# WeatherStation.net
KiCad netlist of a schematic drawn in EAGLE
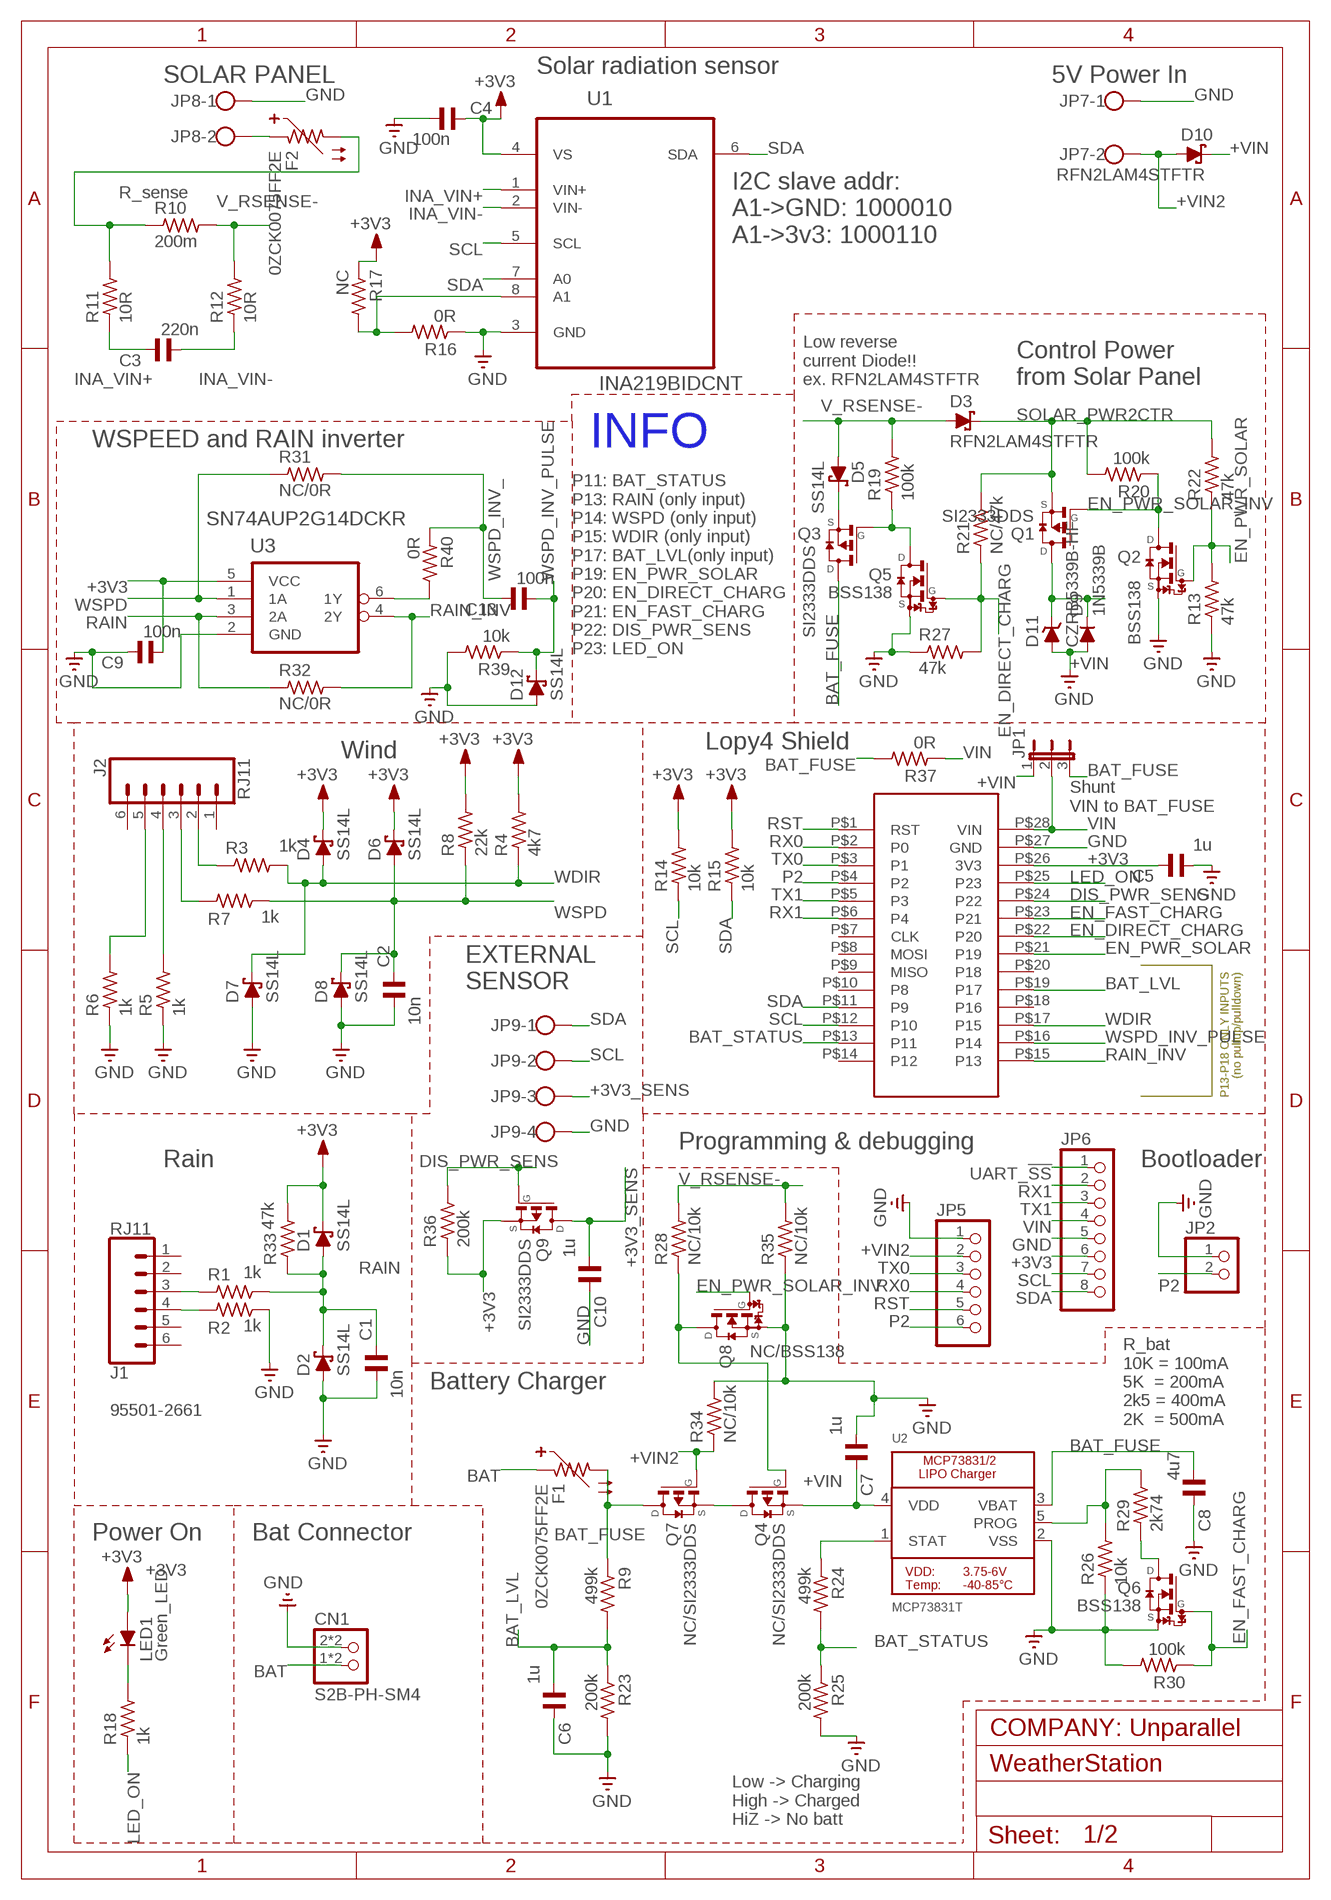
[diagram p0: schematic, sheet 1]
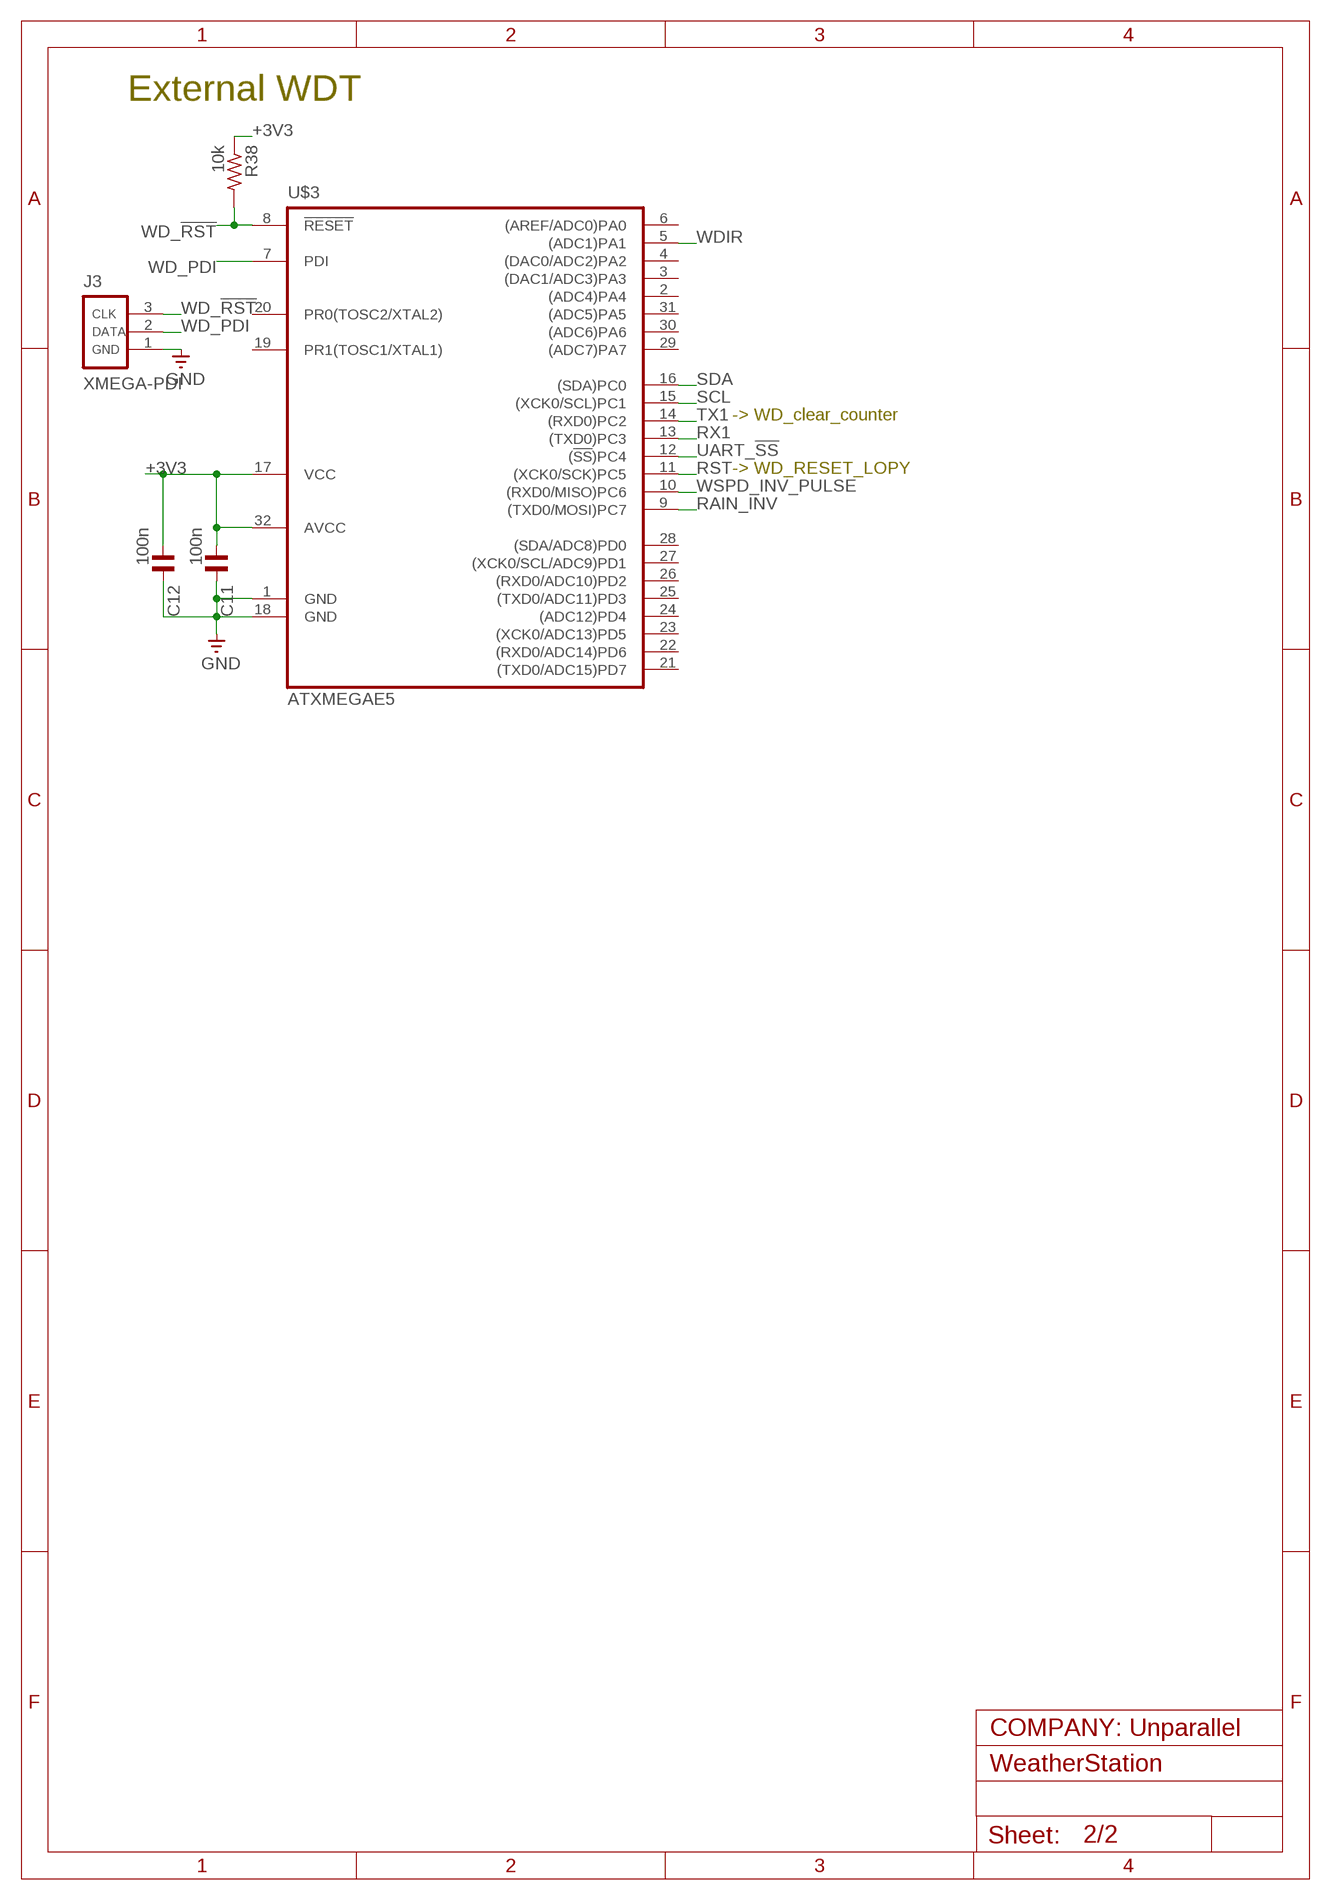
[diagram p1: schematic, sheet 2]

(export (version "E")
  (design (tool "Eeschema 10.0.6"))
  (components
    (comp (ref "C11")
      (value "100n")
      (footprint "eagle-import:C0603")
      (libsource (lib "eagle-import") (part "C-EUC0603"))
    )
    (comp (ref "C12")
      (value "100n")
      (footprint "eagle-import:C0603")
      (libsource (lib "eagle-import") (part "C-EUC0603"))
    )
    (comp (ref "J3")
      (value "XMEGA-PDI")
      (footprint "eagle-import:HDR-MA02-3P_P0.05_FABIO")
      (libsource (lib "eagle-import") (part "XMEGA-PDI-3_FABIO"))
    )
    (comp (ref "R38")
      (value "10k")
      (footprint "eagle-import:R0603")
      (libsource (lib "eagle-import") (part "R-EU_R0603"))
    )
    (comp (ref "U$3")
      (value "ATXMEGAE5")
      (footprint "eagle-import:TQFP32_PROTO_SLIM")
      (libsource (lib "eagle-import") (part "ATXMEGAE5-AU_SLIM_AU"))
    )
    (comp (ref "C1")
      (value "10n")
      (footprint "eagle-import:C0603_C0805_PROTO_SLIM")
      (libsource (lib "eagle-import") (part "C-EUC0603/C0805_PROTO_SLIM"))
    )
    (comp (ref "C2")
      (value "10n")
      (footprint "eagle-import:C0603_C0805_PROTO_SLIM")
      (libsource (lib "eagle-import") (part "C-EUC0603/C0805_PROTO_SLIM"))
    )
    (comp (ref "C3")
      (value "220n")
      (footprint "eagle-import:C0603")
      (libsource (lib "eagle-import") (part "C-EUC0603"))
    )
    (comp (ref "C4")
      (value "100n")
      (footprint "eagle-import:C0603")
      (libsource (lib "eagle-import") (part "C-EUC0603"))
    )
    (comp (ref "C5")
      (value "1u")
      (footprint "eagle-import:C0603_C0805_PROTO_SLIM")
      (libsource (lib "eagle-import") (part "C-EUC0603/C0805_PROTO_SLIM"))
    )
    (comp (ref "C6")
      (value "1u")
      (footprint "eagle-import:C0603_C0805_PROTO_SLIM")
      (libsource (lib "eagle-import") (part "C-EUC0603/C0805_PROTO_SLIM"))
    )
    (comp (ref "C7")
      (value "1u")
      (footprint "eagle-import:C0603_C0805_PROTO_SLIM")
      (libsource (lib "eagle-import") (part "C-EUC0603/C0805_PROTO_SLIM"))
    )
    (comp (ref "C8")
      (value "4u7")
      (footprint "eagle-import:C0603_C0805_PROTO_SLIM")
      (libsource (lib "eagle-import") (part "C-EUC0603/C0805_PROTO_SLIM"))
    )
    (comp (ref "C9")
      (value "100n")
      (footprint "eagle-import:C0603")
      (libsource (lib "eagle-import") (part "C-EUC0603"))
    )
    (comp (ref "C10")
      (value "1u")
      (footprint "eagle-import:C0603_C0805_PROTO_SLIM")
      (libsource (lib "eagle-import") (part "C-EUC0603/C0805_PROTO_SLIM"))
    )
    (comp (ref "C13")
      (value "100n")
      (footprint "eagle-import:C0603")
      (libsource (lib "eagle-import") (part "C-EUC0603"))
    )
    (comp (ref "CN1")
      (value "S2B-PH-SM4")
      (footprint "eagle-import:JST-PH-2-SMT-RA_OK")
      (libsource (lib "eagle-import") (part "JST_2PINHOR_VER"))
    )
    (comp (ref "D1")
      (value "SS14L")
      (footprint "eagle-import:SUB_SMA_PROTO")
      (libsource (lib "eagle-import") (part "SCHOTTKY-DIODESUB_SMA_PROTO"))
    )
    (comp (ref "D2")
      (value "SS14L")
      (footprint "eagle-import:SUB_SMA_PROTO")
      (libsource (lib "eagle-import") (part "SCHOTTKY-DIODESUB_SMA_PROTO"))
    )
    (comp (ref "D3")
      (value "RFN2LAM4STFTR")
      (footprint "eagle-import:SMA_SOD-128_PROTO")
      (libsource (lib "eagle-import") (part "SCHOTTKY-DIODESMA_SOD-128_PROTO"))
    )
    (comp (ref "D4")
      (value "SS14L")
      (footprint "eagle-import:SUB_SMA_PROTO")
      (libsource (lib "eagle-import") (part "SCHOTTKY-DIODESUB_SMA_PROTO"))
    )
    (comp (ref "D5")
      (value "SS14L")
      (footprint "eagle-import:SUB_SMA_PROTO")
      (libsource (lib "eagle-import") (part "SCHOTTKY-DIODESUB_SMA_PROTO"))
    )
    (comp (ref "D6")
      (value "SS14L")
      (footprint "eagle-import:SUB_SMA_PROTO")
      (libsource (lib "eagle-import") (part "SCHOTTKY-DIODESUB_SMA_PROTO"))
    )
    (comp (ref "D7")
      (value "SS14L")
      (footprint "eagle-import:SUB_SMA_PROTO")
      (libsource (lib "eagle-import") (part "SCHOTTKY-DIODESUB_SMA_PROTO"))
    )
    (comp (ref "D8")
      (value "SS14L")
      (footprint "eagle-import:SUB_SMA_PROTO")
      (libsource (lib "eagle-import") (part "SCHOTTKY-DIODESUB_SMA_PROTO"))
    )
    (comp (ref "D9")
      (value "1N5339B")
      (footprint "eagle-import:DO15-12")
      (libsource (lib "eagle-import") (part "DIODE-DO15-12"))
    )
    (comp (ref "D10")
      (value "RFN2LAM4STFTR")
      (footprint "eagle-import:SMA_SOD-128_PROTO")
      (libsource (lib "eagle-import") (part "SCHOTTKY-DIODESMA_SOD-128_PROTO"))
    )
    (comp (ref "D11")
      (value "CZRB5339B-HF")
      (footprint "eagle-import:SMB_PROTO")
      (libsource (lib "eagle-import") (part "ZENER-DIODE-PROTO"))
    )
    (comp (ref "D12")
      (value "SS14L")
      (footprint "eagle-import:SUB_SMA_PROTO")
      (libsource (lib "eagle-import") (part "SCHOTTKY-DIODESUB_SMA_PROTO"))
    )
    (comp (ref "F1")
      (value "0ZCK0075FF2E")
      (footprint "eagle-import:R0603_R0805_PROTO_SLIM")
      (libsource (lib "eagle-import") (part "PTC-0603_0805_PROTO_SLIM"))
    )
    (comp (ref "F2")
      (value "0ZCK0075FF2E")
      (footprint "eagle-import:R0603_R0805_PROTO_SLIM")
      (libsource (lib "eagle-import") (part "PTC-0603_0805_PROTO_SLIM"))
    )
    (comp (ref "J1")
      (value "RJ11")
      (footprint "eagle-import:RJ11-6")
      (libsource (lib "eagle-import") (part "RJ11-6"))
    )
    (comp (ref "J2")
      (value "RJ11")
      (footprint "eagle-import:RJ11-6")
      (libsource (lib "eagle-import") (part "RJ11-6"))
    )
    (comp (ref "JP1")
      (value "JP2E-0805")
      (footprint "eagle-import:R0805_2")
      (libsource (lib "eagle-import") (part "JP2E-0805"))
    )
    (comp (ref "JP2")
      (value "PINHD-1X2")
      (footprint "eagle-import:1X02")
      (libsource (lib "eagle-import") (part "PINHD-1X2"))
    )
    (comp (ref "JP5")
      (value "PINHD-1X6")
      (footprint "eagle-import:1X06")
      (libsource (lib "eagle-import") (part "PINHD-1X6"))
    )
    (comp (ref "JP6")
      (value "PINHD-1X8")
      (footprint "eagle-import:1X08")
      (libsource (lib "eagle-import") (part "PINHD-1X8"))
    )
    (comp (ref "JP7")
      (value "W237-102")
      (footprint "eagle-import:W237-102")
      (libsource (lib "eagle-import") (part "W237-102"))
    )
    (comp (ref "JP8")
      (value "W237-102")
      (footprint "eagle-import:W237-102")
      (libsource (lib "eagle-import") (part "W237-102"))
    )
    (comp (ref "JP9")
      (value "W237-4")
      (footprint "eagle-import:W237-4")
      (libsource (lib "eagle-import") (part "W237-4"))
    )
    (comp (ref "LED1")
      (value "Green_LED")
      (footprint "eagle-import:CHIP-LED0805")
      (libsource (lib "eagle-import") (part "LEDCHIP-LED0805"))
    )
    (comp (ref "Q1")
      (value "SI2333DDS")
      (footprint "eagle-import:SOT23_PROTO_SLIM")
      (libsource (lib "eagle-import") (part "SI2333DDSPROTO_SLIM"))
    )
    (comp (ref "Q2")
      (value "BSS138")
      (footprint "eagle-import:SOT23_PROTO_SLIM")
      (libsource (lib "eagle-import") (part "NX7002AKPROTO_SLIM"))
    )
    (comp (ref "Q3")
      (value "SI2333DDS")
      (footprint "eagle-import:SOT23_PROTO_SLIM")
      (libsource (lib "eagle-import") (part "SI2333DDSPROTO_SLIM"))
    )
    (comp (ref "Q4")
      (value "NC/SI2333DDS")
      (footprint "eagle-import:SOT23_PROTO_SLIM")
      (libsource (lib "eagle-import") (part "SI2333DDSPROTO_SLIM"))
    )
    (comp (ref "Q5")
      (value "BSS138")
      (footprint "eagle-import:SOT23_PROTO_SLIM")
      (libsource (lib "eagle-import") (part "NX7002AKPROTO_SLIM"))
    )
    (comp (ref "Q6")
      (value "BSS138")
      (footprint "eagle-import:SOT23_PROTO_SLIM")
      (libsource (lib "eagle-import") (part "NX7002AKPROTO_SLIM"))
    )
    (comp (ref "Q7")
      (value "NC/SI2333DDS")
      (footprint "eagle-import:SOT23_PROTO_SLIM")
      (libsource (lib "eagle-import") (part "SI2333DDSPROTO_SLIM"))
    )
    (comp (ref "Q8")
      (value "NC/BSS138")
      (footprint "eagle-import:SOT23_PROTO_SLIM")
      (libsource (lib "eagle-import") (part "NX7002AKPROTO_SLIM"))
    )
    (comp (ref "Q9")
      (value "SI2333DDS")
      (footprint "eagle-import:SOT23_PROTO_SLIM")
      (libsource (lib "eagle-import") (part "SI2333DDSPROTO_SLIM"))
    )
    (comp (ref "R1")
      (value "1k")
      (footprint "eagle-import:R0603")
      (libsource (lib "eagle-import") (part "R-EU_R0603"))
    )
    (comp (ref "R2")
      (value "1k")
      (footprint "eagle-import:R0603")
      (libsource (lib "eagle-import") (part "R-EU_R0603"))
    )
    (comp (ref "R3")
      (value "1k")
      (footprint "eagle-import:R0603")
      (libsource (lib "eagle-import") (part "R-EU_R0603"))
    )
    (comp (ref "R4")
      (value "4k7")
      (footprint "eagle-import:R0603")
      (libsource (lib "eagle-import") (part "R-EU_R0603"))
    )
    (comp (ref "R5")
      (value "1k")
      (footprint "eagle-import:R0603")
      (libsource (lib "eagle-import") (part "R-EU_R0603"))
    )
    (comp (ref "R6")
      (value "1k")
      (footprint "eagle-import:R0603")
      (libsource (lib "eagle-import") (part "R-EU_R0603"))
    )
    (comp (ref "R7")
      (value "1k")
      (footprint "eagle-import:R0603")
      (libsource (lib "eagle-import") (part "R-EU_R0603"))
    )
    (comp (ref "R8")
      (value "22k")
      (footprint "eagle-import:R0603")
      (libsource (lib "eagle-import") (part "R-EU_R0603"))
    )
    (comp (ref "R9")
      (value "499k")
      (footprint "eagle-import:R0603_R0805_PROTO_SLIM")
      (libsource (lib "eagle-import") (part "R-EU_R0603/R0805_PROTO_SLIM"))
    )
    (comp (ref "R10")
      (value "200m")
      (footprint "eagle-import:R0603_R0805_PROTO_SLIM")
      (libsource (lib "eagle-import") (part "R-EU_R0603/R0805_PROTO_SLIM"))
    )
    (comp (ref "R11")
      (value "10R")
      (footprint "eagle-import:R0603")
      (libsource (lib "eagle-import") (part "R-EU_R0603"))
    )
    (comp (ref "R12")
      (value "10R")
      (footprint "eagle-import:R0603")
      (libsource (lib "eagle-import") (part "R-EU_R0603"))
    )
    (comp (ref "R13")
      (value "47k")
      (footprint "eagle-import:R0603")
      (libsource (lib "eagle-import") (part "R-EU_R0603"))
    )
    (comp (ref "R14")
      (value "10k")
      (footprint "eagle-import:R0603")
      (libsource (lib "eagle-import") (part "R-EU_R0603"))
    )
    (comp (ref "R15")
      (value "10k")
      (footprint "eagle-import:R0603")
      (libsource (lib "eagle-import") (part "R-EU_R0603"))
    )
    (comp (ref "R16")
      (value "0R")
      (footprint "eagle-import:R0603")
      (libsource (lib "eagle-import") (part "R-EU_R0603"))
    )
    (comp (ref "R17")
      (value "NC")
      (footprint "eagle-import:R0603")
      (libsource (lib "eagle-import") (part "R-EU_R0603"))
    )
    (comp (ref "R18")
      (value "1k")
      (footprint "eagle-import:R0603")
      (libsource (lib "eagle-import") (part "R-EU_R0603"))
    )
    (comp (ref "R19")
      (value "100k")
      (footprint "eagle-import:R0603")
      (libsource (lib "eagle-import") (part "R-EU_R0603"))
    )
    (comp (ref "R20")
      (value "100k")
      (footprint "eagle-import:R0603")
      (libsource (lib "eagle-import") (part "R-EU_R0603"))
    )
    (comp (ref "R21")
      (value "NC/47k")
      (footprint "eagle-import:R0603")
      (libsource (lib "eagle-import") (part "R-EU_R0603"))
    )
    (comp (ref "R22")
      (value "47k")
      (footprint "eagle-import:R0603")
      (libsource (lib "eagle-import") (part "R-EU_R0603"))
    )
    (comp (ref "R23")
      (value "200k")
      (footprint "eagle-import:R0603_R0805_PROTO_SLIM")
      (libsource (lib "eagle-import") (part "R-EU_R0603/R0805_PROTO_SLIM"))
    )
    (comp (ref "R24")
      (value "499k")
      (footprint "eagle-import:R0603_R0805_PROTO_SLIM")
      (libsource (lib "eagle-import") (part "R-EU_R0603/R0805_PROTO_SLIM"))
    )
    (comp (ref "R25")
      (value "200k")
      (footprint "eagle-import:R0603_R0805_PROTO_SLIM")
      (libsource (lib "eagle-import") (part "R-EU_R0603/R0805_PROTO_SLIM"))
    )
    (comp (ref "R26")
      (value "10k")
      (footprint "eagle-import:R0603")
      (libsource (lib "eagle-import") (part "R-EU_R0603"))
    )
    (comp (ref "R27")
      (value "47k")
      (footprint "eagle-import:R0603")
      (libsource (lib "eagle-import") (part "R-EU_R0603"))
    )
    (comp (ref "R28")
      (value "NC/10k")
      (footprint "eagle-import:R0603")
      (libsource (lib "eagle-import") (part "R-EU_R0603"))
    )
    (comp (ref "R29")
      (value "2k74")
      (footprint "eagle-import:R0603_R0805_PROTO_SLIM")
      (libsource (lib "eagle-import") (part "R-EU_R0603/R0805_PROTO_SLIM"))
    )
    (comp (ref "R30")
      (value "100k")
      (footprint "eagle-import:R0603")
      (libsource (lib "eagle-import") (part "R-EU_R0603"))
    )
    (comp (ref "R31")
      (value "NC/0R")
      (footprint "eagle-import:R0603")
      (libsource (lib "eagle-import") (part "R-EU_R0603"))
    )
    (comp (ref "R32")
      (value "NC/0R")
      (footprint "eagle-import:R0603")
      (libsource (lib "eagle-import") (part "R-EU_R0603"))
    )
    (comp (ref "R33")
      (value "47k")
      (footprint "eagle-import:R0603")
      (libsource (lib "eagle-import") (part "R-EU_R0603"))
    )
    (comp (ref "R34")
      (value "NC/10k")
      (footprint "eagle-import:R0603")
      (libsource (lib "eagle-import") (part "R-EU_R0603"))
    )
    (comp (ref "R35")
      (value "NC/10k")
      (footprint "eagle-import:R0603")
      (libsource (lib "eagle-import") (part "R-EU_R0603"))
    )
    (comp (ref "R36")
      (value "200k")
      (footprint "eagle-import:R0603_R0805_PROTO_SLIM")
      (libsource (lib "eagle-import") (part "R-EU_R0603/R0805_PROTO_SLIM"))
    )
    (comp (ref "R37")
      (value "0R")
      (footprint "eagle-import:R0603")
      (libsource (lib "eagle-import") (part "R-EU_R0603"))
    )
    (comp (ref "R39")
      (value "10k")
      (footprint "eagle-import:R0603")
      (libsource (lib "eagle-import") (part "R-EU_R0603"))
    )
    (comp (ref "R40")
      (value "0R")
      (footprint "eagle-import:R0603")
      (libsource (lib "eagle-import") (part "R-EU_R0603"))
    )
    (comp (ref "U$2")
      (value "LOPY4_SHIELD")
      (footprint "eagle-import:LOPY4_SHIELD")
      (libsource (lib "eagle-import") (part "LOPY4_SHIELD"))
    )
    (comp (ref "U1")
      (value "INA219BIDCNT")
      (footprint "eagle-import:SOT65P280X145-8N")
      (libsource (lib "eagle-import") (part "INA219BIDCNT"))
    )
    (comp (ref "U2")
      (value "MCP73831T")
      (footprint "eagle-import:SOT23-5")
      (libsource (lib "eagle-import") (part "MCP73831/2"))
    )
    (comp (ref "U3")
      (value "SN74AUP2G14DCKR")
      (footprint "eagle-import:SOT65P210X110-6N_EDIT")
      (libsource (lib "eagle-import") (part "SN74AUP2G14-DCKR"))
    )
  )
  (nets
    (net (code "1") (name "+3V3") (class "Default")
      (node (ref "C11") (pin "2") (pinfunction "2_2") (pintype "passive"))
      (node (ref "C12") (pin "2") (pinfunction "2_2") (pintype "passive"))
      (node (ref "C4") (pin "1") (pinfunction "1_1") (pintype "passive"))
      (node (ref "C5") (pin "1") (pinfunction "1_1") (pintype "passive"))
      (node (ref "C9") (pin "2") (pinfunction "2_2") (pintype "passive"))
      (node (ref "D1") (pin "C") (pinfunction "C_C") (pintype "passive"))
      (node (ref "D4") (pin "C") (pinfunction "C_C") (pintype "passive"))
      (node (ref "D6") (pin "C") (pinfunction "C_C") (pintype "passive"))
      (node (ref "JP6") (pin "6") (pinfunction "6_6") (pintype "passive"))
      (node (ref "LED1") (pin "A") (pinfunction "A_A") (pintype "passive"))
      (node (ref "Q9") (pin "2") (pinfunction "S_2") (pintype "passive"))
      (node (ref "R14") (pin "2") (pinfunction "2_2") (pintype "passive"))
      (node (ref "R15") (pin "2") (pinfunction "2_2") (pintype "passive"))
      (node (ref "R17") (pin "1") (pinfunction "1_1") (pintype "passive"))
      (node (ref "R33") (pin "2") (pinfunction "2_2") (pintype "passive"))
      (node (ref "R36") (pin "1") (pinfunction "1_1") (pintype "passive"))
      (node (ref "R38") (pin "1") (pinfunction "1_1") (pintype "passive"))
      (node (ref "R4") (pin "2") (pinfunction "2_2") (pintype "passive"))
      (node (ref "R8") (pin "2") (pinfunction "2_2") (pintype "passive"))
      (node (ref "U$2") (pin "P$26") (pinfunction "3V3_P$26") (pintype "power_in"))
      (node (ref "U$3") (pin "17") (pinfunction "VCC_17") (pintype "power_in"))
      (node (ref "U$3") (pin "32") (pinfunction "AVCC_32") (pintype "power_in"))
      (node (ref "U1") (pin "4") (pinfunction "VS_4") (pintype "power_in"))
      (node (ref "U3") (pin "5") (pinfunction "VCC_5") (pintype "power_in"))
    )
    (net (code "2") (name "+3V3_SENS") (class "Default")
      (node (ref "C10") (pin "2") (pinfunction "2_2") (pintype "passive"))
      (node (ref "JP9") (pin "3") (pinfunction "KL_3") (pintype "passive"))
      (node (ref "Q9") (pin "3") (pinfunction "D_3") (pintype "passive"))
    )
    (net (code "3") (name "+VIN") (class "Default")
      (node (ref "C7") (pin "1") (pinfunction "1_1") (pintype "passive"))
      (node (ref "D10") (pin "C") (pinfunction "C_C") (pintype "passive"))
      (node (ref "D11") (pin "C") (pinfunction "C_C") (pintype "passive"))
      (node (ref "D9") (pin "C") (pinfunction "C_C") (pintype "passive"))
      (node (ref "JP1") (pin "1") (pinfunction "1_1") (pintype "passive"))
      (node (ref "Q1") (pin "3") (pinfunction "D_3") (pintype "passive"))
      (node (ref "Q4") (pin "2") (pinfunction "S_2") (pintype "passive"))
      (node (ref "U2") (pin "4") (pinfunction "VDD_4") (pintype "power_in"))
    )
    (net (code "4") (name "+VIN2") (class "Default")
      (node (ref "D10") (pin "A") (pinfunction "A_A") (pintype "passive"))
      (node (ref "JP5") (pin "2") (pinfunction "2_2") (pintype "passive"))
      (node (ref "JP7") (pin "2") (pinfunction "KL_2") (pintype "passive"))
      (node (ref "Q7") (pin "1") (pinfunction "G_1") (pintype "passive"))
      (node (ref "R34") (pin "1") (pinfunction "1_1") (pintype "passive"))
    )
    (net (code "5") (name "BAT") (class "Default")
      (node (ref "CN1") (pin "1") (pinfunction "2_1") (pintype "passive"))
      (node (ref "CN1") (pin "3") (pinfunction "2_3") (pintype "passive"))
      (node (ref "F1") (pin "1") (pinfunction "1_1") (pintype "passive"))
    )
    (net (code "6") (name "BAT_FUSE") (class "Default")
      (node (ref "C8") (pin "2") (pinfunction "2_2") (pintype "passive"))
      (node (ref "F1") (pin "2") (pinfunction "2_2") (pintype "passive"))
      (node (ref "JP1") (pin "3") (pinfunction "3_3") (pintype "passive"))
      (node (ref "Q3") (pin "3") (pinfunction "D_3") (pintype "passive"))
      (node (ref "Q7") (pin "3") (pinfunction "D_3") (pintype "passive"))
      (node (ref "R37") (pin "2") (pinfunction "2_2") (pintype "passive"))
      (node (ref "R9") (pin "1") (pinfunction "1_1") (pintype "passive"))
      (node (ref "U2") (pin "3") (pinfunction "VBAT_3") (pintype "power_in"))
    )
    (net (code "7") (name "BAT_LVL") (class "Default")
      (node (ref "C6") (pin "2") (pinfunction "2_2") (pintype "passive"))
      (node (ref "R23") (pin "1") (pinfunction "1_1") (pintype "passive"))
      (node (ref "R9") (pin "2") (pinfunction "2_2") (pintype "passive"))
      (node (ref "U$2") (pin "P$19") (pinfunction "P17_P$19") (pintype "bidirectional"))
    )
    (net (code "8") (name "BAT_STATUS") (class "Default")
      (node (ref "R24") (pin "2") (pinfunction "2_2") (pintype "passive"))
      (node (ref "R25") (pin "1") (pinfunction "1_1") (pintype "passive"))
      (node (ref "U$2") (pin "P$13") (pinfunction "P11_P$13") (pintype "bidirectional"))
    )
    (net (code "9") (name "DIS_PWR_SENS") (class "Default")
      (node (ref "Q9") (pin "1") (pinfunction "G_1") (pintype "passive"))
      (node (ref "R36") (pin "2") (pinfunction "2_2") (pintype "passive"))
      (node (ref "U$2") (pin "P$24") (pinfunction "P22_P$24") (pintype "bidirectional"))
    )
    (net (code "10") (name "EN_DIRECT_CHARG") (class "Default")
      (node (ref "Q5") (pin "1") (pinfunction "G_1") (pintype "passive"))
      (node (ref "R21") (pin "1") (pinfunction "1_1") (pintype "passive"))
      (node (ref "R27") (pin "2") (pinfunction "2_2") (pintype "passive"))
      (node (ref "U$2") (pin "P$22") (pinfunction "P20_P$22") (pintype "bidirectional"))
    )
    (net (code "11") (name "EN_FAST_CHARG") (class "Default")
      (node (ref "Q6") (pin "1") (pinfunction "G_1") (pintype "passive"))
      (node (ref "R30") (pin "1") (pinfunction "1_1") (pintype "passive"))
      (node (ref "U$2") (pin "P$23") (pinfunction "P21_P$23") (pintype "bidirectional"))
    )
    (net (code "12") (name "EN_PWR_SOLAR") (class "Default")
      (node (ref "Q2") (pin "1") (pinfunction "G_1") (pintype "passive"))
      (node (ref "R13") (pin "2") (pinfunction "2_2") (pintype "passive"))
      (node (ref "R22") (pin "1") (pinfunction "1_1") (pintype "passive"))
      (node (ref "U$2") (pin "P$21") (pinfunction "P19_P$21") (pintype "bidirectional"))
    )
    (net (code "13") (name "EN_PWR_SOLAR_INV") (class "Default")
      (node (ref "Q1") (pin "1") (pinfunction "G_1") (pintype "passive"))
      (node (ref "Q2") (pin "3") (pinfunction "D_3") (pintype "passive"))
      (node (ref "Q8") (pin "1") (pinfunction "G_1") (pintype "passive"))
      (node (ref "R20") (pin "1") (pinfunction "1_1") (pintype "passive"))
    )
    (net (code "14") (name "GND") (class "Default")
      (node (ref "C1") (pin "2") (pinfunction "2_2") (pintype "passive"))
      (node (ref "C10") (pin "1") (pinfunction "1_1") (pintype "passive"))
      (node (ref "C11") (pin "1") (pinfunction "1_1") (pintype "passive"))
      (node (ref "C12") (pin "1") (pinfunction "1_1") (pintype "passive"))
      (node (ref "C2") (pin "2") (pinfunction "2_2") (pintype "passive"))
      (node (ref "C4") (pin "2") (pinfunction "2_2") (pintype "passive"))
      (node (ref "C5") (pin "2") (pinfunction "2_2") (pintype "passive"))
      (node (ref "C6") (pin "1") (pinfunction "1_1") (pintype "passive"))
      (node (ref "C7") (pin "2") (pinfunction "2_2") (pintype "passive"))
      (node (ref "C8") (pin "1") (pinfunction "1_1") (pintype "passive"))
      (node (ref "C9") (pin "1") (pinfunction "1_1") (pintype "passive"))
      (node (ref "CN1") (pin "2") (pinfunction "1_2") (pintype "passive"))
      (node (ref "CN1") (pin "4") (pinfunction "1_4") (pintype "passive"))
      (node (ref "D11") (pin "A") (pinfunction "A_A") (pintype "passive"))
      (node (ref "D12") (pin "A") (pinfunction "A_A") (pintype "passive"))
      (node (ref "D2") (pin "A") (pinfunction "A_A") (pintype "passive"))
      (node (ref "D7") (pin "A") (pinfunction "A_A") (pintype "passive"))
      (node (ref "D8") (pin "A") (pinfunction "A_A") (pintype "passive"))
      (node (ref "D9") (pin "A") (pinfunction "A_A") (pintype "passive"))
      (node (ref "J3") (pin "1") (pinfunction "1_1") (pintype "passive"))
      (node (ref "JP2") (pin "1") (pinfunction "1_1") (pintype "passive"))
      (node (ref "JP5") (pin "1") (pinfunction "1_1") (pintype "passive"))
      (node (ref "JP6") (pin "5") (pinfunction "5_5") (pintype "passive"))
      (node (ref "JP7") (pin "1") (pinfunction "KL_1") (pintype "passive"))
      (node (ref "JP8") (pin "1") (pinfunction "KL_1") (pintype "passive"))
      (node (ref "JP9") (pin "4") (pinfunction "KL_4") (pintype "passive"))
      (node (ref "Q2") (pin "2") (pinfunction "S_2") (pintype "passive"))
      (node (ref "Q5") (pin "2") (pinfunction "S_2") (pintype "passive"))
      (node (ref "Q6") (pin "2") (pinfunction "S_2") (pintype "passive"))
      (node (ref "Q8") (pin "2") (pinfunction "S_2") (pintype "passive"))
      (node (ref "R13") (pin "1") (pinfunction "1_1") (pintype "passive"))
      (node (ref "R16") (pin "1") (pinfunction "1_1") (pintype "passive"))
      (node (ref "R2") (pin "2") (pinfunction "2_2") (pintype "passive"))
      (node (ref "R23") (pin "2") (pinfunction "2_2") (pintype "passive"))
      (node (ref "R25") (pin "2") (pinfunction "2_2") (pintype "passive"))
      (node (ref "R26") (pin "1") (pinfunction "1_1") (pintype "passive"))
      (node (ref "R27") (pin "1") (pinfunction "1_1") (pintype "passive"))
      (node (ref "R30") (pin "2") (pinfunction "2_2") (pintype "passive"))
      (node (ref "R34") (pin "2") (pinfunction "2_2") (pintype "passive"))
      (node (ref "R35") (pin "1") (pinfunction "1_1") (pintype "passive"))
      (node (ref "R39") (pin "2") (pinfunction "2_2") (pintype "passive"))
      (node (ref "R5") (pin "1") (pinfunction "1_1") (pintype "passive"))
      (node (ref "R6") (pin "1") (pinfunction "1_1") (pintype "passive"))
      (node (ref "U$2") (pin "P$27") (pinfunction "GND_P$27") (pintype "power_in"))
      (node (ref "U$3") (pin "1") (pinfunction "GND_1") (pintype "power_in"))
      (node (ref "U$3") (pin "18") (pinfunction "GND_18") (pintype "power_in"))
      (node (ref "U1") (pin "3") (pinfunction "GND_3") (pintype "passive"))
      (node (ref "U2") (pin "2") (pinfunction "VSS_2") (pintype "power_in"))
      (node (ref "U3") (pin "2") (pinfunction "GND_2") (pintype "passive"))
    )
    (net (code "15") (name "INA_VIN+") (class "Default")
      (node (ref "C3") (pin "1") (pinfunction "1_1") (pintype "passive"))
      (node (ref "R11") (pin "1") (pinfunction "1_1") (pintype "passive"))
      (node (ref "U1") (pin "1") (pinfunction "VIN+_1") (pintype "power_in"))
    )
    (net (code "16") (name "INA_VIN-") (class "Default")
      (node (ref "C3") (pin "2") (pinfunction "2_2") (pintype "passive"))
      (node (ref "R12") (pin "1") (pinfunction "1_1") (pintype "passive"))
      (node (ref "U1") (pin "2") (pinfunction "VIN-_2") (pintype "power_in"))
    )
    (net (code "17") (name "LED_ON") (class "Default")
      (node (ref "R18") (pin "1") (pinfunction "1_1") (pintype "passive"))
      (node (ref "U$2") (pin "P$25") (pinfunction "P23_P$25") (pintype "bidirectional"))
    )
    (net (code "18") (name "Net-(F2-Pad2)") (class "Default")
      (node (ref "F2") (pin "2") (pinfunction "2_2") (pintype "passive"))
      (node (ref "R10") (pin "1") (pinfunction "1_1") (pintype "passive"))
      (node (ref "R11") (pin "2") (pinfunction "2_2") (pintype "passive"))
    )
    (net (code "19") (name "Net-(J1-Pad3)") (class "Default")
      (node (ref "J1") (pin "3") (pinfunction "3_3") (pintype "passive"))
      (node (ref "R1") (pin "1") (pinfunction "1_1") (pintype "passive"))
    )
    (net (code "20") (name "Net-(J1-Pad4)") (class "Default")
      (node (ref "J1") (pin "4") (pinfunction "4_4") (pintype "passive"))
      (node (ref "R2") (pin "1") (pinfunction "1_1") (pintype "passive"))
    )
    (net (code "21") (name "Net-(J2-Pad2)") (class "Default")
      (node (ref "J2") (pin "2") (pinfunction "2_2") (pintype "passive"))
      (node (ref "R3") (pin "1") (pinfunction "1_1") (pintype "passive"))
    )
    (net (code "22") (name "Net-(J2-Pad3)") (class "Default")
      (node (ref "J2") (pin "3") (pinfunction "3_3") (pintype "passive"))
      (node (ref "R7") (pin "1") (pinfunction "1_1") (pintype "passive"))
    )
    (net (code "23") (name "Net-(J2-Pad4)") (class "Default")
      (node (ref "J2") (pin "4") (pinfunction "4_4") (pintype "passive"))
      (node (ref "R5") (pin "2") (pinfunction "2_2") (pintype "passive"))
    )
    (net (code "24") (name "Net-(J2-Pad5)") (class "Default")
      (node (ref "J2") (pin "5") (pinfunction "5_5") (pintype "passive"))
      (node (ref "R6") (pin "2") (pinfunction "2_2") (pintype "passive"))
    )
    (net (code "25") (name "Net-(JP8B-KL)") (class "Default")
      (node (ref "F2") (pin "1") (pinfunction "1_1") (pintype "passive"))
      (node (ref "JP8") (pin "2") (pinfunction "KL_2") (pintype "passive"))
    )
    (net (code "26") (name "Net-(LED1-PadC)") (class "Default")
      (node (ref "LED1") (pin "C") (pinfunction "C_C") (pintype "passive"))
      (node (ref "R18") (pin "2") (pinfunction "2_2") (pintype "passive"))
    )
    (net (code "27") (name "Net-(Q3-G)") (class "Default")
      (node (ref "Q3") (pin "1") (pinfunction "G_1") (pintype "passive"))
      (node (ref "Q5") (pin "3") (pinfunction "D_3") (pintype "passive"))
      (node (ref "R19") (pin "1") (pinfunction "1_1") (pintype "passive"))
    )
    (net (code "28") (name "Net-(Q3-S)") (class "Default")
      (node (ref "D5") (pin "C") (pinfunction "C_C") (pintype "passive"))
      (node (ref "Q3") (pin "2") (pinfunction "S_2") (pintype "passive"))
    )
    (net (code "29") (name "Net-(Q4-D)") (class "Default")
      (node (ref "Q4") (pin "3") (pinfunction "D_3") (pintype "passive"))
      (node (ref "Q7") (pin "2") (pinfunction "S_2") (pintype "passive"))
    )
    (net (code "30") (name "Net-(Q4-G)") (class "Default")
      (node (ref "Q4") (pin "1") (pinfunction "G_1") (pintype "passive"))
      (node (ref "Q8") (pin "3") (pinfunction "D_3") (pintype "passive"))
      (node (ref "R28") (pin "1") (pinfunction "1_1") (pintype "passive"))
    )
    (net (code "31") (name "Net-(Q6-D)") (class "Default")
      (node (ref "Q6") (pin "3") (pinfunction "D_3") (pintype "passive"))
      (node (ref "R29") (pin "1") (pinfunction "1_1") (pintype "passive"))
    )
    (net (code "32") (name "Net-(U1-A1)") (class "Default")
      (node (ref "R16") (pin "2") (pinfunction "2_2") (pintype "passive"))
      (node (ref "R17") (pin "2") (pinfunction "2_2") (pintype "passive"))
      (node (ref "U1") (pin "8") (pinfunction "A1_8") (pintype "input"))
    )
    (net (code "33") (name "Net-(U2-PROG)") (class "Default")
      (node (ref "R26") (pin "2") (pinfunction "2_2") (pintype "passive"))
      (node (ref "R29") (pin "2") (pinfunction "2_2") (pintype "passive"))
      (node (ref "U2") (pin "5") (pinfunction "PROG_5") (pintype "input"))
    )
    (net (code "34") (name "Net-(U2-STAT)") (class "Default")
      (node (ref "R24") (pin "1") (pinfunction "1_1") (pintype "passive"))
      (node (ref "U2") (pin "1") (pinfunction "STAT_1") (pintype "output"))
    )
    (net (code "35") (name "Net-(U3-1Y)") (class "Default")
      (node (ref "R40") (pin "2") (pinfunction "2_2") (pintype "passive"))
      (node (ref "U3") (pin "6") (pinfunction "1Y_6") (pintype "output"))
    )
    (net (code "36") (name "P2") (class "Default")
      (node (ref "JP2") (pin "2") (pinfunction "2_2") (pintype "passive"))
      (node (ref "JP5") (pin "6") (pinfunction "6_6") (pintype "passive"))
      (node (ref "U$2") (pin "P$4") (pinfunction "P2_P$4") (pintype "bidirectional"))
    )
    (net (code "37") (name "RAIN") (class "Default")
      (node (ref "C1") (pin "1") (pinfunction "1_1") (pintype "passive"))
      (node (ref "D1") (pin "A") (pinfunction "A_A") (pintype "passive"))
      (node (ref "D2") (pin "C") (pinfunction "C_C") (pintype "passive"))
      (node (ref "R1") (pin "2") (pinfunction "2_2") (pintype "passive"))
      (node (ref "R32") (pin "1") (pinfunction "1_1") (pintype "passive"))
      (node (ref "R33") (pin "1") (pinfunction "1_1") (pintype "passive"))
      (node (ref "U3") (pin "3") (pinfunction "2A_3") (pintype "input"))
    )
    (net (code "38") (name "RAIN_INV") (class "Default")
      (node (ref "R32") (pin "2") (pinfunction "2_2") (pintype "passive"))
      (node (ref "U$2") (pin "P$15") (pinfunction "P13_P$15") (pintype "bidirectional"))
      (node (ref "U$3") (pin "9") (pinfunction "(TXD0/MOSI)PC7_9") (pintype "bidirectional"))
      (node (ref "U3") (pin "4") (pinfunction "2Y_4") (pintype "output"))
    )
    (net (code "39") (name "RST") (class "Default")
      (node (ref "JP5") (pin "5") (pinfunction "5_5") (pintype "passive"))
      (node (ref "U$2") (pin "P$1") (pinfunction "RST_P$1") (pintype "input"))
      (node (ref "U$3") (pin "11") (pinfunction "(XCK0/SCK)PC5_11") (pintype "bidirectional"))
    )
    (net (code "40") (name "RX0") (class "Default")
      (node (ref "JP5") (pin "4") (pinfunction "4_4") (pintype "passive"))
      (node (ref "U$2") (pin "P$2") (pinfunction "P0_P$2") (pintype "bidirectional"))
    )
    (net (code "41") (name "RX1") (class "Default")
      (node (ref "JP6") (pin "2") (pinfunction "2_2") (pintype "passive"))
      (node (ref "U$2") (pin "P$6") (pinfunction "P4_P$6") (pintype "bidirectional"))
      (node (ref "U$3") (pin "13") (pinfunction "(TXD0)PC3_13") (pintype "bidirectional"))
    )
    (net (code "42") (name "SCL") (class "Default")
      (node (ref "JP6") (pin "7") (pinfunction "7_7") (pintype "passive"))
      (node (ref "JP9") (pin "2") (pinfunction "KL_2") (pintype "passive"))
      (node (ref "R14") (pin "1") (pinfunction "1_1") (pintype "passive"))
      (node (ref "U$2") (pin "P$12") (pinfunction "P10_P$12") (pintype "bidirectional"))
      (node (ref "U$3") (pin "15") (pinfunction "(XCK0/SCL)PC1_15") (pintype "bidirectional"))
      (node (ref "U1") (pin "5") (pinfunction "SCL_5") (pintype "input"))
    )
    (net (code "43") (name "SDA") (class "Default")
      (node (ref "JP6") (pin "8") (pinfunction "8_8") (pintype "passive"))
      (node (ref "JP9") (pin "1") (pinfunction "KL_1") (pintype "passive"))
      (node (ref "R15") (pin "1") (pinfunction "1_1") (pintype "passive"))
      (node (ref "U$2") (pin "P$11") (pinfunction "P9_P$11") (pintype "bidirectional"))
      (node (ref "U$3") (pin "16") (pinfunction "(SDA)PC0_16") (pintype "bidirectional"))
      (node (ref "U1") (pin "6") (pinfunction "SDA_6") (pintype "bidirectional"))
      (node (ref "U1") (pin "7") (pinfunction "A0_7") (pintype "input"))
    )
    (net (code "44") (name "SOLAR_PWR2CTR") (class "Default")
      (node (ref "D3") (pin "C") (pinfunction "C_C") (pintype "passive"))
      (node (ref "Q1") (pin "2") (pinfunction "S_2") (pintype "passive"))
      (node (ref "R20") (pin "2") (pinfunction "2_2") (pintype "passive"))
      (node (ref "R21") (pin "2") (pinfunction "2_2") (pintype "passive"))
      (node (ref "R22") (pin "2") (pinfunction "2_2") (pintype "passive"))
    )
    (net (code "45") (name "TX0") (class "Default")
      (node (ref "JP5") (pin "3") (pinfunction "3_3") (pintype "passive"))
      (node (ref "U$2") (pin "P$3") (pinfunction "P1_P$3") (pintype "bidirectional"))
    )
    (net (code "46") (name "TX1") (class "Default")
      (node (ref "JP6") (pin "3") (pinfunction "3_3") (pintype "passive"))
      (node (ref "U$2") (pin "P$5") (pinfunction "P3_P$5") (pintype "bidirectional"))
      (node (ref "U$3") (pin "14") (pinfunction "(RXD0)PC2_14") (pintype "bidirectional"))
    )
    (net (code "47") (name "UART_~{SS}") (class "Default")
      (node (ref "JP6") (pin "1") (pinfunction "1_1") (pintype "passive"))
      (node (ref "U$3") (pin "12") (pinfunction "(~{SS})PC4_12") (pintype "bidirectional"))
    )
    (net (code "48") (name "VIN") (class "Default")
      (node (ref "JP1") (pin "2") (pinfunction "2_2") (pintype "passive"))
      (node (ref "JP6") (pin "4") (pinfunction "4_4") (pintype "passive"))
      (node (ref "R37") (pin "1") (pinfunction "1_1") (pintype "passive"))
      (node (ref "U$2") (pin "P$28") (pinfunction "VIN_P$28") (pintype "power_in"))
    )
    (net (code "49") (name "V_RSENSE-") (class "Default")
      (node (ref "D3") (pin "A") (pinfunction "A_A") (pintype "passive"))
      (node (ref "D5") (pin "A") (pinfunction "A_A") (pintype "passive"))
      (node (ref "R10") (pin "2") (pinfunction "2_2") (pintype "passive"))
      (node (ref "R12") (pin "2") (pinfunction "2_2") (pintype "passive"))
      (node (ref "R19") (pin "2") (pinfunction "2_2") (pintype "passive"))
      (node (ref "R28") (pin "2") (pinfunction "2_2") (pintype "passive"))
      (node (ref "R35") (pin "2") (pinfunction "2_2") (pintype "passive"))
    )
    (net (code "50") (name "WDIR") (class "Default")
      (node (ref "D4") (pin "A") (pinfunction "A_A") (pintype "passive"))
      (node (ref "D7") (pin "C") (pinfunction "C_C") (pintype "passive"))
      (node (ref "R3") (pin "2") (pinfunction "2_2") (pintype "passive"))
      (node (ref "R4") (pin "1") (pinfunction "1_1") (pintype "passive"))
      (node (ref "U$2") (pin "P$17") (pinfunction "P15_P$17") (pintype "bidirectional"))
      (node (ref "U$3") (pin "5") (pinfunction "(ADC1)PA1_5") (pintype "bidirectional"))
    )
    (net (code "51") (name "WD_PDI") (class "Default")
      (node (ref "J3") (pin "2") (pinfunction "2_2") (pintype "passive"))
      (node (ref "U$3") (pin "7") (pinfunction "PDI_7") (pintype "input"))
    )
    (net (code "52") (name "WD_~{RST}") (class "Default")
      (node (ref "J3") (pin "3") (pinfunction "3_3") (pintype "passive"))
      (node (ref "R38") (pin "2") (pinfunction "2_2") (pintype "passive"))
      (node (ref "U$3") (pin "8") (pinfunction "~{RESET}_8") (pintype "input"))
    )
    (net (code "53") (name "WSPD") (class "Default")
      (node (ref "C2") (pin "1") (pinfunction "1_1") (pintype "passive"))
      (node (ref "D6") (pin "A") (pinfunction "A_A") (pintype "passive"))
      (node (ref "D8") (pin "C") (pinfunction "C_C") (pintype "passive"))
      (node (ref "R31") (pin "1") (pinfunction "1_1") (pintype "passive"))
      (node (ref "R7") (pin "2") (pinfunction "2_2") (pintype "passive"))
      (node (ref "R8") (pin "1") (pinfunction "1_1") (pintype "passive"))
      (node (ref "U3") (pin "1") (pinfunction "1A_1") (pintype "input"))
    )
    (net (code "54") (name "WSPD_INV_") (class "Default")
      (node (ref "C13") (pin "1") (pinfunction "1_1") (pintype "passive"))
      (node (ref "R31") (pin "2") (pinfunction "2_2") (pintype "passive"))
      (node (ref "R40") (pin "1") (pinfunction "1_1") (pintype "passive"))
    )
    (net (code "55") (name "WSPD_INV_PULSE") (class "Default")
      (node (ref "C13") (pin "2") (pinfunction "2_2") (pintype "passive"))
      (node (ref "D12") (pin "C") (pinfunction "C_C") (pintype "passive"))
      (node (ref "R39") (pin "1") (pinfunction "1_1") (pintype "passive"))
      (node (ref "U$2") (pin "P$16") (pinfunction "P14_P$16") (pintype "bidirectional"))
      (node (ref "U$3") (pin "10") (pinfunction "(RXD0/MISO)PC6_10") (pintype "bidirectional"))
    )
    (net (code "56") (name "unconnected-(J1-Pad1)") (class "Default")
      (node (ref "J1") (pin "1") (pinfunction "1_1") (pintype "passive"))
    )
    (net (code "57") (name "unconnected-(J1-Pad2)") (class "Default")
      (node (ref "J1") (pin "2") (pinfunction "2_2") (pintype "passive"))
    )
    (net (code "58") (name "unconnected-(J1-Pad5)") (class "Default")
      (node (ref "J1") (pin "5") (pinfunction "5_5") (pintype "passive"))
    )
    (net (code "59") (name "unconnected-(J1-Pad6)") (class "Default")
      (node (ref "J1") (pin "6") (pinfunction "6_6") (pintype "passive"))
    )
    (net (code "60") (name "unconnected-(J2-Pad1)") (class "Default")
      (node (ref "J2") (pin "1") (pinfunction "1_1") (pintype "passive"))
    )
    (net (code "61") (name "unconnected-(J2-Pad6)") (class "Default")
      (node (ref "J2") (pin "6") (pinfunction "6_6") (pintype "passive"))
    )
    (net (code "62") (name "unconnected-(U$2-CLK-PadP$7)") (class "Default")
      (node (ref "U$2") (pin "P$7") (pinfunction "CLK_P$7") (pintype "bidirectional"))
    )
    (net (code "63") (name "unconnected-(U$2-MISO-PadP$9)") (class "Default")
      (node (ref "U$2") (pin "P$9") (pinfunction "MISO_P$9") (pintype "bidirectional"))
    )
    (net (code "64") (name "unconnected-(U$2-MOSI-PadP$8)") (class "Default")
      (node (ref "U$2") (pin "P$8") (pinfunction "MOSI_P$8") (pintype "bidirectional"))
    )
    (net (code "65") (name "unconnected-(U$2-P8-PadP$10)") (class "Default")
      (node (ref "U$2") (pin "P$10") (pinfunction "P8_P$10") (pintype "bidirectional"))
    )
    (net (code "66") (name "unconnected-(U$2-P12-PadP$14)") (class "Default")
      (node (ref "U$2") (pin "P$14") (pinfunction "P12_P$14") (pintype "bidirectional"))
    )
    (net (code "67") (name "unconnected-(U$2-P16-PadP$18)") (class "Default")
      (node (ref "U$2") (pin "P$18") (pinfunction "P16_P$18") (pintype "bidirectional"))
    )
    (net (code "68") (name "unconnected-(U$2-P18-PadP$20)") (class "Default")
      (node (ref "U$2") (pin "P$20") (pinfunction "P18_P$20") (pintype "bidirectional"))
    )
    (net (code "69") (name "unconnected-(U$3-(ADC4)PA4-Pad2)") (class "Default")
      (node (ref "U$3") (pin "2") (pinfunction "(ADC4)PA4_2") (pintype "bidirectional"))
    )
    (net (code "70") (name "unconnected-(U$3-(ADC5)PA5-Pad31)") (class "Default")
      (node (ref "U$3") (pin "31") (pinfunction "(ADC5)PA5_31") (pintype "bidirectional"))
    )
    (net (code "71") (name "unconnected-(U$3-(ADC6)PA6-Pad30)") (class "Default")
      (node (ref "U$3") (pin "30") (pinfunction "(ADC6)PA6_30") (pintype "bidirectional"))
    )
    (net (code "72") (name "unconnected-(U$3-(ADC7)PA7-Pad29)") (class "Default")
      (node (ref "U$3") (pin "29") (pinfunction "(ADC7)PA7_29") (pintype "bidirectional"))
    )
    (net (code "73") (name "unconnected-(U$3-(ADC12)PD4-Pad24)") (class "Default")
      (node (ref "U$3") (pin "24") (pinfunction "(ADC12)PD4_24") (pintype "bidirectional"))
    )
    (net (code "74") (name "unconnected-(U$3-(AREF{slash}ADC0)PA0-Pad6)") (class "Default")
      (node (ref "U$3") (pin "6") (pinfunction "(AREF/ADC0)PA0_6") (pintype "bidirectional"))
    )
    (net (code "75") (name "unconnected-(U$3-(DAC0{slash}ADC2)PA2-Pad4)") (class "Default")
      (node (ref "U$3") (pin "4") (pinfunction "(DAC0/ADC2)PA2_4") (pintype "bidirectional"))
    )
    (net (code "76") (name "unconnected-(U$3-(DAC1{slash}ADC3)PA3-Pad3)") (class "Default")
      (node (ref "U$3") (pin "3") (pinfunction "(DAC1/ADC3)PA3_3") (pintype "bidirectional"))
    )
    (net (code "77") (name "unconnected-(U$3-(RXD0{slash}ADC10)PD2-Pad26)") (class "Default")
      (node (ref "U$3") (pin "26") (pinfunction "(RXD0/ADC10)PD2_26") (pintype "bidirectional"))
    )
    (net (code "78") (name "unconnected-(U$3-(RXD0{slash}ADC14)PD6-Pad22)") (class "Default")
      (node (ref "U$3") (pin "22") (pinfunction "(RXD0/ADC14)PD6_22") (pintype "bidirectional"))
    )
    (net (code "79") (name "unconnected-(U$3-(SDA{slash}ADC8)PD0-Pad28)") (class "Default")
      (node (ref "U$3") (pin "28") (pinfunction "(SDA/ADC8)PD0_28") (pintype "bidirectional"))
    )
    (net (code "80") (name "unconnected-(U$3-(TXD0{slash}ADC11)PD3-Pad25)") (class "Default")
      (node (ref "U$3") (pin "25") (pinfunction "(TXD0/ADC11)PD3_25") (pintype "bidirectional"))
    )
    (net (code "81") (name "unconnected-(U$3-(TXD0{slash}ADC15)PD7-Pad21)") (class "Default")
      (node (ref "U$3") (pin "21") (pinfunction "(TXD0/ADC15)PD7_21") (pintype "bidirectional"))
    )
    (net (code "82") (name "unconnected-(U$3-(XCK0{slash}ADC13)PD5-Pad23)") (class "Default")
      (node (ref "U$3") (pin "23") (pinfunction "(XCK0/ADC13)PD5_23") (pintype "bidirectional"))
    )
    (net (code "83") (name "unconnected-(U$3-(XCK0{slash}SCL{slash}ADC9)PD1-Pad27)") (class "Default")
      (node (ref "U$3") (pin "27") (pinfunction "(XCK0/SCL/ADC9)PD1_27") (pintype "bidirectional"))
    )
    (net (code "84") (name "unconnected-(U$3-PR0(TOSC2{slash}XTAL2)-Pad20)") (class "Default")
      (node (ref "U$3") (pin "20") (pinfunction "PR0(TOSC2/XTAL2)_20") (pintype "bidirectional"))
    )
    (net (code "85") (name "unconnected-(U$3-PR1(TOSC1{slash}XTAL1)-Pad19)") (class "Default")
      (node (ref "U$3") (pin "19") (pinfunction "PR1(TOSC1/XTAL1)_19") (pintype "bidirectional"))
    )
  )
)
